# Pico_Stringer_Sch.net
KiCad netlist of a schematic drawn in Altium Designer
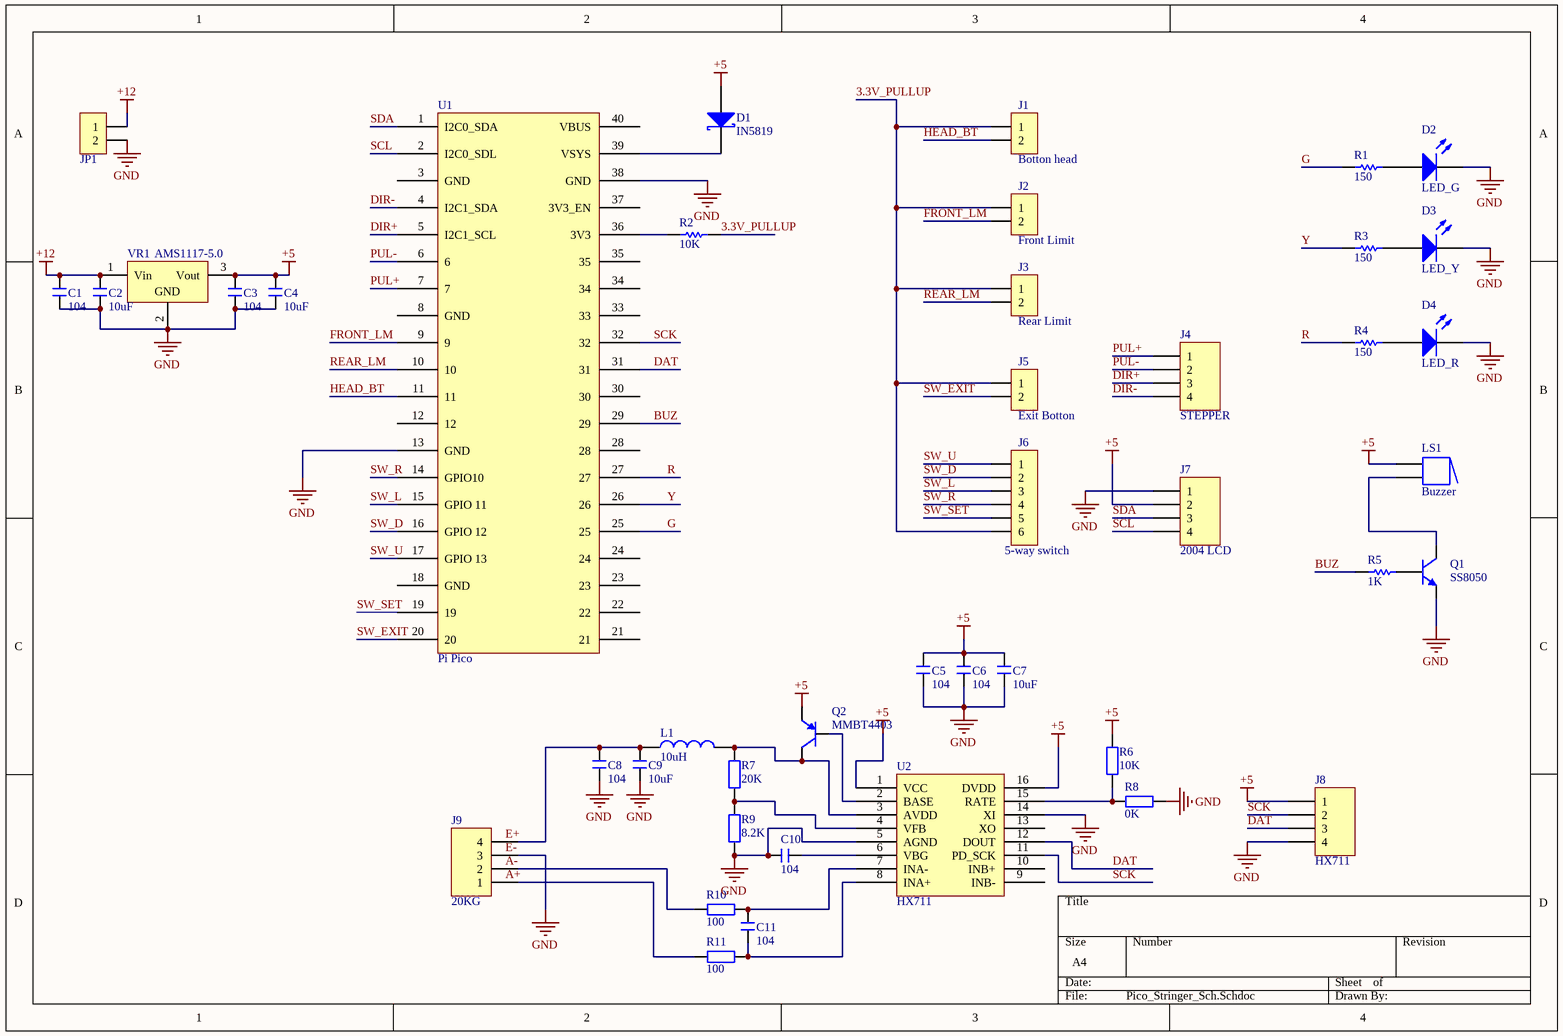
[diagram p0: Pico_Stringer_Sch.Schdoc]

(export (version "E")
  (design (tool "Eeschema 10.0.6"))
  (components
    (comp (ref "C1")
      (value "104")
      (footprint "6-0805_M")
      (description "贴片电容")
      (libsource (lib "0.1 - 电阻-电容-电感") (part "C"))
    )
    (comp (ref "C2")
      (value "10uF")
      (footprint "C1210_M")
      (description "贴片电容")
      (libsource (lib "0.1 - 电阻-电容-电感") (part "C"))
    )
    (comp (ref "C3")
      (value "104")
      (footprint "6-0805_M")
      (description "贴片电容")
      (libsource (lib "0.1 - 电阻-电容-电感") (part "C"))
    )
    (comp (ref "C4")
      (value "10uF")
      (footprint "C1210_M")
      (description "贴片电容")
      (libsource (lib "0.1 - 电阻-电容-电感") (part "C"))
    )
    (comp (ref "C5")
      (value "104")
      (footprint "6-0805_M")
      (description "贴片电容")
      (libsource (lib "0.1 - 电阻-电容-电感") (part "C"))
    )
    (comp (ref "C6")
      (value "104")
      (footprint "6-0805_M")
      (description "贴片电容")
      (libsource (lib "0.1 - 电阻-电容-电感") (part "C"))
    )
    (comp (ref "C7")
      (value "10uF")
      (footprint "C1210_M")
      (description "贴片电容")
      (libsource (lib "0.1 - 电阻-电容-电感") (part "C"))
    )
    (comp (ref "C8")
      (value "104")
      (footprint "6-0805_M")
      (description "贴片电容")
      (libsource (lib "0.1 - 电阻-电容-电感") (part "C"))
    )
    (comp (ref "C9")
      (value "10uF")
      (footprint "C1210_M")
      (description "贴片电容")
      (libsource (lib "0.1 - 电阻-电容-电感") (part "C"))
    )
    (comp (ref "C10")
      (value "104")
      (footprint "6-0805_M")
      (description "贴片电容")
      (libsource (lib "0.1 - 电阻-电容-电感") (part "C"))
    )
    (comp (ref "C11")
      (value "104")
      (footprint "6-0805_M")
      (description "贴片电容")
      (libsource (lib "0.1 - 电阻-电容-电感") (part "C"))
    )
    (comp (ref "D1")
      (value "IN5819")
      (footprint "DO-41")
      (description "Schottky Diode")
      (fields (field (name "PUBLISHER") "Altium Limited"))
      (libsource (lib "Miscellaneous Devices") (part "D Schottky"))
    )
    (comp (ref "D2")
      (value "LED_G")
      (footprint "Normal Use for Rubasse:10mm LED")
      (description "Typical RED, GREEN, YELLOW, AMBER GaAs LED")
      (fields (field (name "PUBLISHER") "Altium Limited"))
      (libsource (lib "Miscellaneous Devices") (part "LED2"))
    )
    (comp (ref "D3")
      (value "LED_Y")
      (footprint "Normal Use for Rubasse:10mm LED")
      (description "Typical RED, GREEN, YELLOW, AMBER GaAs LED")
      (fields (field (name "PUBLISHER") "Altium Limited"))
      (libsource (lib "Miscellaneous Devices") (part "LED2"))
    )
    (comp (ref "D4")
      (value "LED_R")
      (footprint "Normal Use for Rubasse:10mm LED")
      (description "Typical RED, GREEN, YELLOW, AMBER GaAs LED")
      (fields (field (name "PUBLISHER") "Altium Limited"))
      (libsource (lib "Miscellaneous Devices") (part "LED2"))
    )
    (comp (ref "J1")
      (value "Botton head")
      (footprint "XH2.54-LI-2P")
      (description "2P接插件")
      (fields (field (name "版权归属") "封装库来自淘宝 ID：黄晶宝石"))
      (libsource (lib "5.4 - 接插件-脚距2.54 (100mil) ") (part "Header 2"))
    )
    (comp (ref "J2")
      (value "Front Limit")
      (footprint "XH2.54-LI-2P")
      (description "2P接插件")
      (fields (field (name "版权归属") "封装库来自淘宝 ID：黄晶宝石"))
      (libsource (lib "5.4 - 接插件-脚距2.54 (100mil) ") (part "Header 2"))
    )
    (comp (ref "J3")
      (value "Rear Limit")
      (footprint "XH2.54-LI-2P")
      (description "2P接插件")
      (fields (field (name "版权归属") "封装库来自淘宝 ID：黄晶宝石"))
      (libsource (lib "5.4 - 接插件-脚距2.54 (100mil) ") (part "Header 2"))
    )
    (comp (ref "J4")
      (value "STEPPER")
      (footprint "XH2.54-LI-4P")
      (description "DIR PUL")
      (fields (field (name "PUBLISHER") "Altium Limited"))
      (libsource (lib "Miscellaneous Connectors") (part "Header 4"))
    )
    (comp (ref "J5")
      (value "Exit Botton")
      (footprint "12x12mm SWITCH")
      (description "2P接插件")
      (fields (field (name "版权归属") "封装库来自淘宝 ID：黄晶宝石"))
      (libsource (lib "5.4 - 接插件-脚距2.54 (100mil) ") (part "Header 2"))
    )
    (comp (ref "J6")
      (value "5-way switch")
      (footprint "5WAY_SWITCH")
      (description "6P接插件")
      (fields (field (name "版权归属") "封装库来自淘宝 ID：黄晶宝石"))
      (libsource (lib "5.4 - 接插件-脚距2.54 (100mil) ") (part "Header 6"))
    )
    (comp (ref "J7")
      (value "2004 LCD")
      (footprint "HDR1X4")
      (description "2004 I2C LCD")
      (fields (field (name "PUBLISHER") "Altium Limited"))
      (libsource (lib "Miscellaneous Connectors") (part "Header 4"))
    )
    (comp (ref "J8")
      (value "HX711")
      (footprint "HX711_MODULE")
      (description "HX711 module")
      (fields (field (name "PUBLISHER") "Altium Limited"))
      (libsource (lib "Miscellaneous Connectors") (part "Header 4"))
    )
    (comp (ref "J9")
      (value "20KG")
      (footprint "HDR1X4")
      (description "Keyes Hx711 module")
      (fields (field (name "PUBLISHER") "Altium Limited"))
      (libsource (lib "") (part "Header 4_1"))
    )
    (comp (ref "JP1")
      (value "HDR-1X2")
      (footprint "XH2.54-LI-2P")
      (description "5V")
      (fields (field (name "版权归属") "封装库来自淘宝 ID：黄晶宝石"))
      (libsource (lib "") (part "Header 2_1"))
    )
    (comp (ref "L1")
      (value "10uH")
      (footprint "L 1210")
      (description "小功率贴片电感")
      (libsource (lib "0.1 - 电阻-电容-电感") (part "L"))
    )
    (comp (ref "LS1")
      (value "Buzzer")
      (footprint "Buzzer")
      (description "Magnetic Transducer Buzzer")
      (fields (field (name "PUBLISHER") "Altium Limited"))
      (libsource (lib "Miscellaneous Devices") (part "Buzzer"))
    )
    (comp (ref "Q1")
      (value "SS8050")
      (footprint "TO92A")
      (description "高频放大-NPN型")
      (fields (field (name "版权归属") "封装库来自淘宝 ID：黄晶宝石"))
      (libsource (lib "0.4 - 三极管") (part "8050-DIP"))
    )
    (comp (ref "Q2")
      (value "MMBT4403")
      (footprint "SOT23-3L")
      (description "高频放大-PNP型")
      (fields (field (name "版权归属") "封装库来自淘宝 ID：黄晶宝石"))
      (libsource (lib "0.4 - 三极管") (part "8550-SMD"))
    )
    (comp (ref "R1")
      (value "150")
      (footprint "AXIAL-0.3")
      (description "Resistor")
      (fields (field (name "PUBLISHER") "Altium Limited"))
      (libsource (lib "Miscellaneous Devices") (part "Res1"))
    )
    (comp (ref "R2")
      (value "10K")
      (footprint "AXIAL-0.3")
      (description "Resistor")
      (fields (field (name "PUBLISHER") "Altium Limited"))
      (libsource (lib "Miscellaneous Devices") (part "Res1"))
    )
    (comp (ref "R3")
      (value "150")
      (footprint "AXIAL-0.3")
      (description "Resistor")
      (fields (field (name "PUBLISHER") "Altium Limited"))
      (libsource (lib "Miscellaneous Devices") (part "Res1"))
    )
    (comp (ref "R4")
      (value "150")
      (footprint "AXIAL-0.3")
      (description "Resistor")
      (fields (field (name "PUBLISHER") "Altium Limited"))
      (libsource (lib "Miscellaneous Devices") (part "Res1"))
    )
    (comp (ref "R5")
      (value "1K")
      (footprint "AXIAL-0.3")
      (description "Resistor")
      (fields (field (name "PUBLISHER") "Altium Limited"))
      (libsource (lib "Miscellaneous Devices") (part "Res1"))
    )
    (comp (ref "R6")
      (value "10K")
      (footprint "6-0805_N")
      (description "贴片电阻")
      (fields (field (name "版权归属") "来自淘宝 ID：黄晶宝石"))
      (libsource (lib "0.1 - 电阻-电容-电感") (part "R"))
    )
    (comp (ref "R7")
      (value "20K")
      (footprint "6-0805_M")
      (description "贴片电阻")
      (fields (field (name "版权归属") "来自淘宝 ID：黄晶宝石"))
      (libsource (lib "0.1 - 电阻-电容-电感") (part "R"))
    )
    (comp (ref "R8")
      (value "0K")
      (footprint "6-0805_M")
      (description "贴片电阻")
      (fields (field (name "版权归属") "来自淘宝 ID：黄晶宝石"))
      (libsource (lib "0.1 - 电阻-电容-电感") (part "R"))
    )
    (comp (ref "R9")
      (value "8.2K")
      (footprint "6-0805_M")
      (description "贴片电阻")
      (fields (field (name "版权归属") "来自淘宝 ID：黄晶宝石"))
      (libsource (lib "0.1 - 电阻-电容-电感") (part "R"))
    )
    (comp (ref "R10")
      (value "100")
      (footprint "6-0805_M")
      (description "贴片电阻")
      (fields (field (name "版权归属") "来自淘宝 ID：黄晶宝石"))
      (libsource (lib "0.1 - 电阻-电容-电感") (part "R"))
    )
    (comp (ref "R11")
      (value "100")
      (footprint "6-0805_M")
      (description "贴片电阻")
      (fields (field (name "版权归属") "来自淘宝 ID：黄晶宝石"))
      (libsource (lib "0.1 - 电阻-电容-电感") (part "R"))
    )
    (comp (ref "U1") (value "Pi Pico") (footprint "PICO") (libsource (lib "Schlib1") (part "Pi Pico")))
    (comp (ref "U2") (value "HX711") (footprint "SOP16") (libsource (lib "Schlib1") (part "HX711")))
    (comp (ref "VR1")
      (value "AMS1117-5.0")
      (footprint "AMS1117")
      (description "Voltage Regulator")
      (fields (field (name "PUBLISHER") "Altium Limited"))
      (libsource (lib "Miscellaneous Devices") (part "Volt Reg"))
    )
  )
  (nets
    (net (code "1") (name "+5") (class "Default")
      (node (ref "C3") (pin "2") (pinfunction "2_2") (pintype "passive"))
      (node (ref "C4") (pin "2") (pinfunction "2_2") (pintype "passive"))
      (node (ref "C5") (pin "2") (pinfunction "2_2") (pintype "passive"))
      (node (ref "C6") (pin "2") (pinfunction "2_2") (pintype "passive"))
      (node (ref "C7") (pin "2") (pinfunction "2_2") (pintype "passive"))
      (node (ref "D1") (pin "1") (pinfunction "A_1") (pintype "passive"))
      (node (ref "J7") (pin "2") (pinfunction "2_2") (pintype "passive"))
      (node (ref "J8") (pin "1") (pinfunction "1_1") (pintype "passive"))
      (node (ref "LS1") (pin "1") (pinfunction "1_1") (pintype "passive"))
      (node (ref "Q2") (pin "2") (pinfunction "E_2") (pintype "passive"))
      (node (ref "R6") (pin "2") (pinfunction "2_2") (pintype "passive"))
      (node (ref "U2") (pin "1") (pinfunction "VCC_1") (pintype "passive"))
      (node (ref "U2") (pin "16") (pinfunction "DVDD_16") (pintype "passive"))
      (node (ref "VR1") (pin "3") (pinfunction "Vout_3") (pintype "passive"))
    )
    (net (code "2") (name "+12") (class "Default")
      (node (ref "C1") (pin "2") (pinfunction "2_2") (pintype "passive"))
      (node (ref "C2") (pin "2") (pinfunction "2_2") (pintype "passive"))
      (node (ref "JP1") (pin "1") (pinfunction "1_1") (pintype "passive"))
      (node (ref "VR1") (pin "1") (pinfunction "Vin_1") (pintype "passive"))
    )
    (net (code "3") (name "/3.3V_PULLUP") (class "Default")
      (node (ref "J1") (pin "1") (pinfunction "1_1") (pintype "passive"))
      (node (ref "J2") (pin "1") (pinfunction "1_1") (pintype "passive"))
      (node (ref "J3") (pin "1") (pinfunction "1_1") (pintype "passive"))
      (node (ref "J5") (pin "1") (pinfunction "1_1") (pintype "passive"))
      (node (ref "J6") (pin "6") (pinfunction "6_6") (pintype "passive"))
      (node (ref "R2") (pin "2") (pinfunction "2_2") (pintype "passive"))
    )
    (net (code "6") (name "/BUZ") (class "Default")
      (node (ref "R5") (pin "1") (pinfunction "1_1") (pintype "passive"))
      (node (ref "U1") (pin "29") (pinfunction "29_29") (pintype "passive"))
    )
    (net (code "7") (name "/DAT") (class "Default")
      (node (ref "J8") (pin "3") (pinfunction "3_3") (pintype "passive"))
      (node (ref "U1") (pin "31") (pinfunction "31_31") (pintype "passive"))
      (node (ref "U2") (pin "12") (pinfunction "DOUT_12") (pintype "passive"))
    )
    (net (code "8") (name "/DIR+") (class "Default")
      (node (ref "J4") (pin "3") (pinfunction "3_3") (pintype "passive"))
      (node (ref "U1") (pin "5") (pinfunction "I2C1_SCL_5") (pintype "passive"))
    )
    (net (code "9") (name "/DIR-") (class "Default")
      (node (ref "J4") (pin "4") (pinfunction "4_4") (pintype "passive"))
      (node (ref "U1") (pin "4") (pinfunction "I2C1_SDA_4") (pintype "passive"))
    )
    (net (code "12") (name "/FRONT_LM") (class "Default")
      (node (ref "J2") (pin "2") (pinfunction "2_2") (pintype "passive"))
      (node (ref "U1") (pin "9") (pinfunction "9_9") (pintype "passive"))
    )
    (net (code "13") (name "/G") (class "Default")
      (node (ref "R1") (pin "1") (pinfunction "1_1") (pintype "passive"))
      (node (ref "U1") (pin "25") (pinfunction "25_25") (pintype "passive"))
    )
    (net (code "14") (name "/HEAD_BT") (class "Default")
      (node (ref "J1") (pin "2") (pinfunction "2_2") (pintype "passive"))
      (node (ref "U1") (pin "11") (pinfunction "11_11") (pintype "passive"))
    )
    (net (code "15") (name "/PUL+") (class "Default")
      (node (ref "J4") (pin "1") (pinfunction "1_1") (pintype "passive"))
      (node (ref "U1") (pin "7") (pinfunction "7_7") (pintype "passive"))
    )
    (net (code "16") (name "/PUL-") (class "Default")
      (node (ref "J4") (pin "2") (pinfunction "2_2") (pintype "passive"))
      (node (ref "U1") (pin "6") (pinfunction "6_6") (pintype "passive"))
    )
    (net (code "17") (name "/R") (class "Default")
      (node (ref "R4") (pin "1") (pinfunction "1_1") (pintype "passive"))
      (node (ref "U1") (pin "27") (pinfunction "27_27") (pintype "passive"))
    )
    (net (code "18") (name "/REAR_LM") (class "Default")
      (node (ref "J3") (pin "2") (pinfunction "2_2") (pintype "passive"))
      (node (ref "U1") (pin "10") (pinfunction "10_10") (pintype "passive"))
    )
    (net (code "19") (name "/SCK") (class "Default")
      (node (ref "J8") (pin "2") (pinfunction "2_2") (pintype "passive"))
      (node (ref "U1") (pin "32") (pinfunction "32_32") (pintype "passive"))
      (node (ref "U2") (pin "11") (pinfunction "PD_SCK_11") (pintype "passive"))
    )
    (net (code "20") (name "/SCL") (class "Default")
      (node (ref "J7") (pin "4") (pinfunction "4_4") (pintype "passive"))
      (node (ref "U1") (pin "2") (pinfunction "I2C0_SDL_2") (pintype "passive"))
    )
    (net (code "21") (name "/SDA") (class "Default")
      (node (ref "J7") (pin "3") (pinfunction "3_3") (pintype "passive"))
      (node (ref "U1") (pin "1") (pinfunction "I2C0_SDA_1") (pintype "passive"))
    )
    (net (code "22") (name "/SW_D") (class "Default")
      (node (ref "J6") (pin "2") (pinfunction "2_2") (pintype "passive"))
      (node (ref "U1") (pin "16") (pinfunction "GPIO_12_16") (pintype "passive"))
    )
    (net (code "23") (name "/SW_EXIT") (class "Default")
      (node (ref "J5") (pin "2") (pinfunction "2_2") (pintype "passive"))
      (node (ref "U1") (pin "20") (pinfunction "20_20") (pintype "passive"))
    )
    (net (code "24") (name "/SW_L") (class "Default")
      (node (ref "J6") (pin "3") (pinfunction "3_3") (pintype "passive"))
      (node (ref "U1") (pin "15") (pinfunction "GPIO_11_15") (pintype "passive"))
    )
    (net (code "25") (name "/SW_R") (class "Default")
      (node (ref "J6") (pin "4") (pinfunction "4_4") (pintype "passive"))
      (node (ref "U1") (pin "14") (pinfunction "GPIO10_14") (pintype "passive"))
    )
    (net (code "26") (name "/SW_SET") (class "Default")
      (node (ref "J6") (pin "5") (pinfunction "5_5") (pintype "passive"))
      (node (ref "U1") (pin "19") (pinfunction "19_19") (pintype "passive"))
    )
    (net (code "27") (name "/SW_U") (class "Default")
      (node (ref "J6") (pin "1") (pinfunction "1_1") (pintype "passive"))
      (node (ref "U1") (pin "17") (pinfunction "GPIO_13_17") (pintype "passive"))
    )
    (net (code "28") (name "/Y") (class "Default")
      (node (ref "R3") (pin "1") (pinfunction "1_1") (pintype "passive"))
      (node (ref "U1") (pin "26") (pinfunction "26_26") (pintype "passive"))
    )
    (net (code "29") (name "GND") (class "Default")
      (node (ref "C1") (pin "1") (pinfunction "1_1") (pintype "passive"))
      (node (ref "C10") (pin "2") (pinfunction "2_2") (pintype "passive"))
      (node (ref "C2") (pin "1") (pinfunction "1_1") (pintype "passive"))
      (node (ref "C3") (pin "1") (pinfunction "1_1") (pintype "passive"))
      (node (ref "C4") (pin "1") (pinfunction "1_1") (pintype "passive"))
      (node (ref "C5") (pin "1") (pinfunction "1_1") (pintype "passive"))
      (node (ref "C6") (pin "1") (pinfunction "1_1") (pintype "passive"))
      (node (ref "C7") (pin "1") (pinfunction "1_1") (pintype "passive"))
      (node (ref "C8") (pin "1") (pinfunction "1_1") (pintype "passive"))
      (node (ref "C9") (pin "1") (pinfunction "1_1") (pintype "passive"))
      (node (ref "D2") (pin "2") (pinfunction "K_2") (pintype "passive"))
      (node (ref "D3") (pin "2") (pinfunction "K_2") (pintype "passive"))
      (node (ref "D4") (pin "2") (pinfunction "K_2") (pintype "passive"))
      (node (ref "J7") (pin "1") (pinfunction "1_1") (pintype "passive"))
      (node (ref "J8") (pin "4") (pinfunction "4_4") (pintype "passive"))
      (node (ref "J9") (pin "3") (pinfunction "3_3") (pintype "passive"))
      (node (ref "JP1") (pin "2") (pinfunction "2_2") (pintype "passive"))
      (node (ref "Q1") (pin "1") (pinfunction "E_1") (pintype "passive"))
      (node (ref "R8") (pin "1") (pinfunction "1_1") (pintype "passive"))
      (node (ref "R9") (pin "1") (pinfunction "1_1") (pintype "passive"))
      (node (ref "U1") (pin "13") (pinfunction "GND_13") (pintype "passive"))
      (node (ref "U1") (pin "38") (pinfunction "GND_38") (pintype "passive"))
      (node (ref "U2") (pin "14") (pinfunction "XI_14") (pintype "passive"))
      (node (ref "U2") (pin "5") (pinfunction "AGND_5") (pintype "passive"))
      (node (ref "VR1") (pin "2") (pinfunction "GND_2") (pintype "passive"))
    )
    (net (code "30") (name "Net-(C8-Pad2)") (class "Default")
      (node (ref "C8") (pin "2") (pinfunction "2_2") (pintype "passive"))
      (node (ref "C9") (pin "2") (pinfunction "2_2") (pintype "passive"))
      (node (ref "J9") (pin "4") (pinfunction "4_4") (pintype "passive"))
      (node (ref "L1") (pin "1") (pinfunction "1_1") (pintype "passive"))
    )
    (net (code "31") (name "Net-(D1-K)") (class "Default")
      (node (ref "D1") (pin "2") (pinfunction "K_2") (pintype "passive"))
      (node (ref "U1") (pin "39") (pinfunction "VSYS_39") (pintype "passive"))
    )
    (net (code "32") (name "Net-(D2-A)") (class "Default")
      (node (ref "D2") (pin "1") (pinfunction "A_1") (pintype "passive"))
      (node (ref "R1") (pin "2") (pinfunction "2_2") (pintype "passive"))
    )
    (net (code "33") (name "Net-(D3-A)") (class "Default")
      (node (ref "D3") (pin "1") (pinfunction "A_1") (pintype "passive"))
      (node (ref "R3") (pin "2") (pinfunction "2_2") (pintype "passive"))
    )
    (net (code "34") (name "Net-(D4-A)") (class "Default")
      (node (ref "D4") (pin "1") (pinfunction "A_1") (pintype "passive"))
      (node (ref "R4") (pin "2") (pinfunction "2_2") (pintype "passive"))
    )
    (net (code "35") (name "Net-(J9-Pad1)") (class "Default")
      (node (ref "J9") (pin "1") (pinfunction "1_1") (pintype "passive"))
      (node (ref "R11") (pin "1") (pinfunction "1_1") (pintype "passive"))
    )
    (net (code "36") (name "Net-(J9-Pad2)") (class "Default")
      (node (ref "J9") (pin "2") (pinfunction "2_2") (pintype "passive"))
      (node (ref "R10") (pin "1") (pinfunction "1_1") (pintype "passive"))
    )
    (net (code "37") (name "Net-(Q1-B)") (class "Default")
      (node (ref "Q1") (pin "2") (pinfunction "B_2") (pintype "passive"))
      (node (ref "R5") (pin "2") (pinfunction "2_2") (pintype "passive"))
    )
    (net (code "38") (name "Net-(Q1-C)") (class "Default")
      (node (ref "LS1") (pin "2") (pinfunction "2_2") (pintype "passive"))
      (node (ref "Q1") (pin "3") (pinfunction "C_3") (pintype "passive"))
    )
    (net (code "39") (name "Net-(Q2-B)") (class "Default")
      (node (ref "Q2") (pin "1") (pinfunction "B_1") (pintype "passive"))
      (node (ref "U2") (pin "2") (pinfunction "BASE_2") (pintype "passive"))
    )
    (net (code "40") (name "Net-(Q2-C)") (class "Default")
      (node (ref "L1") (pin "2") (pinfunction "2_2") (pintype "passive"))
      (node (ref "Q2") (pin "3") (pinfunction "C_3") (pintype "passive"))
      (node (ref "R7") (pin "2") (pinfunction "2_2") (pintype "passive"))
      (node (ref "U2") (pin "3") (pinfunction "AVDD_3") (pintype "passive"))
    )
    (net (code "41") (name "Net-(U1-3V3)") (class "Default")
      (node (ref "R2") (pin "1") (pinfunction "1_1") (pintype "passive"))
      (node (ref "U1") (pin "36") (pinfunction "3V3_36") (pintype "passive"))
    )
    (net (code "42") (name "Net-(U2-INA+)") (class "Default")
      (node (ref "C11") (pin "1") (pinfunction "1_1") (pintype "passive"))
      (node (ref "R11") (pin "2") (pinfunction "2_2") (pintype "passive"))
      (node (ref "U2") (pin "8") (pinfunction "INA+_8") (pintype "passive"))
    )
    (net (code "43") (name "Net-(U2-INA-)") (class "Default")
      (node (ref "C11") (pin "2") (pinfunction "2_2") (pintype "passive"))
      (node (ref "R10") (pin "2") (pinfunction "2_2") (pintype "passive"))
      (node (ref "U2") (pin "7") (pinfunction "INA-_7") (pintype "passive"))
    )
    (net (code "44") (name "Net-(U2-RATE)") (class "Default")
      (node (ref "R6") (pin "1") (pinfunction "1_1") (pintype "passive"))
      (node (ref "R8") (pin "2") (pinfunction "2_2") (pintype "passive"))
      (node (ref "U2") (pin "15") (pinfunction "RATE_15") (pintype "passive"))
    )
    (net (code "45") (name "Net-(U2-VBG)") (class "Default")
      (node (ref "C10") (pin "1") (pinfunction "1_1") (pintype "passive"))
      (node (ref "U2") (pin "6") (pinfunction "VBG_6") (pintype "passive"))
    )
    (net (code "46") (name "Net-(U2-VFB)") (class "Default")
      (node (ref "R7") (pin "1") (pinfunction "1_1") (pintype "passive"))
      (node (ref "R9") (pin "2") (pinfunction "2_2") (pintype "passive"))
      (node (ref "U2") (pin "4") (pinfunction "VFB_4") (pintype "passive"))
    )
    (net (code "47") (name "unconnected-(U1-3V3_EN-Pad37)") (class "Default")
      (node (ref "U1") (pin "37") (pinfunction "3V3_EN_37") (pintype "passive"))
    )
    (net (code "48") (name "unconnected-(U1-GND-Pad3)") (class "Default")
      (node (ref "U1") (pin "3") (pinfunction "GND_3") (pintype "passive"))
    )
    (net (code "49") (name "unconnected-(U1-GND-Pad8)") (class "Default")
      (node (ref "U1") (pin "8") (pinfunction "GND_8") (pintype "passive"))
    )
    (net (code "50") (name "unconnected-(U1-GND-Pad18)") (class "Default")
      (node (ref "U1") (pin "18") (pinfunction "GND_18") (pintype "passive"))
    )
    (net (code "51") (name "unconnected-(U1-Pad12)") (class "Default")
      (node (ref "U1") (pin "12") (pinfunction "12_12") (pintype "passive"))
    )
    (net (code "52") (name "unconnected-(U1-Pad21)") (class "Default")
      (node (ref "U1") (pin "21") (pinfunction "21_21") (pintype "passive"))
    )
    (net (code "53") (name "unconnected-(U1-Pad22)") (class "Default")
      (node (ref "U1") (pin "22") (pinfunction "22_22") (pintype "passive"))
    )
    (net (code "54") (name "unconnected-(U1-Pad23)") (class "Default")
      (node (ref "U1") (pin "23") (pinfunction "23_23") (pintype "passive"))
    )
    (net (code "55") (name "unconnected-(U1-Pad24)") (class "Default")
      (node (ref "U1") (pin "24") (pinfunction "24_24") (pintype "passive"))
    )
    (net (code "56") (name "unconnected-(U1-Pad28)") (class "Default")
      (node (ref "U1") (pin "28") (pinfunction "28_28") (pintype "passive"))
    )
    (net (code "57") (name "unconnected-(U1-Pad30)") (class "Default")
      (node (ref "U1") (pin "30") (pinfunction "30_30") (pintype "passive"))
    )
    (net (code "58") (name "unconnected-(U1-Pad33)") (class "Default")
      (node (ref "U1") (pin "33") (pinfunction "33_33") (pintype "passive"))
    )
    (net (code "59") (name "unconnected-(U1-Pad34)") (class "Default")
      (node (ref "U1") (pin "34") (pinfunction "34_34") (pintype "passive"))
    )
    (net (code "60") (name "unconnected-(U1-Pad35)") (class "Default")
      (node (ref "U1") (pin "35") (pinfunction "35_35") (pintype "passive"))
    )
    (net (code "61") (name "unconnected-(U1-VBUS-Pad40)") (class "Default")
      (node (ref "U1") (pin "40") (pinfunction "VBUS_40") (pintype "passive"))
    )
    (net (code "62") (name "unconnected-(U2-INB+-Pad10)") (class "Default")
      (node (ref "U2") (pin "10") (pinfunction "INB+_10") (pintype "passive"))
    )
    (net (code "63") (name "unconnected-(U2-INB--Pad9)") (class "Default")
      (node (ref "U2") (pin "9") (pinfunction "INB-_9") (pintype "passive"))
    )
    (net (code "64") (name "unconnected-(U2-XO-Pad13)") (class "Default")
      (node (ref "U2") (pin "13") (pinfunction "XO_13") (pintype "passive"))
    )
  )
)
